# HM-Relais4-v01-002-Umrisse.net
KiCad netlist of a schematic drawn in EAGLE
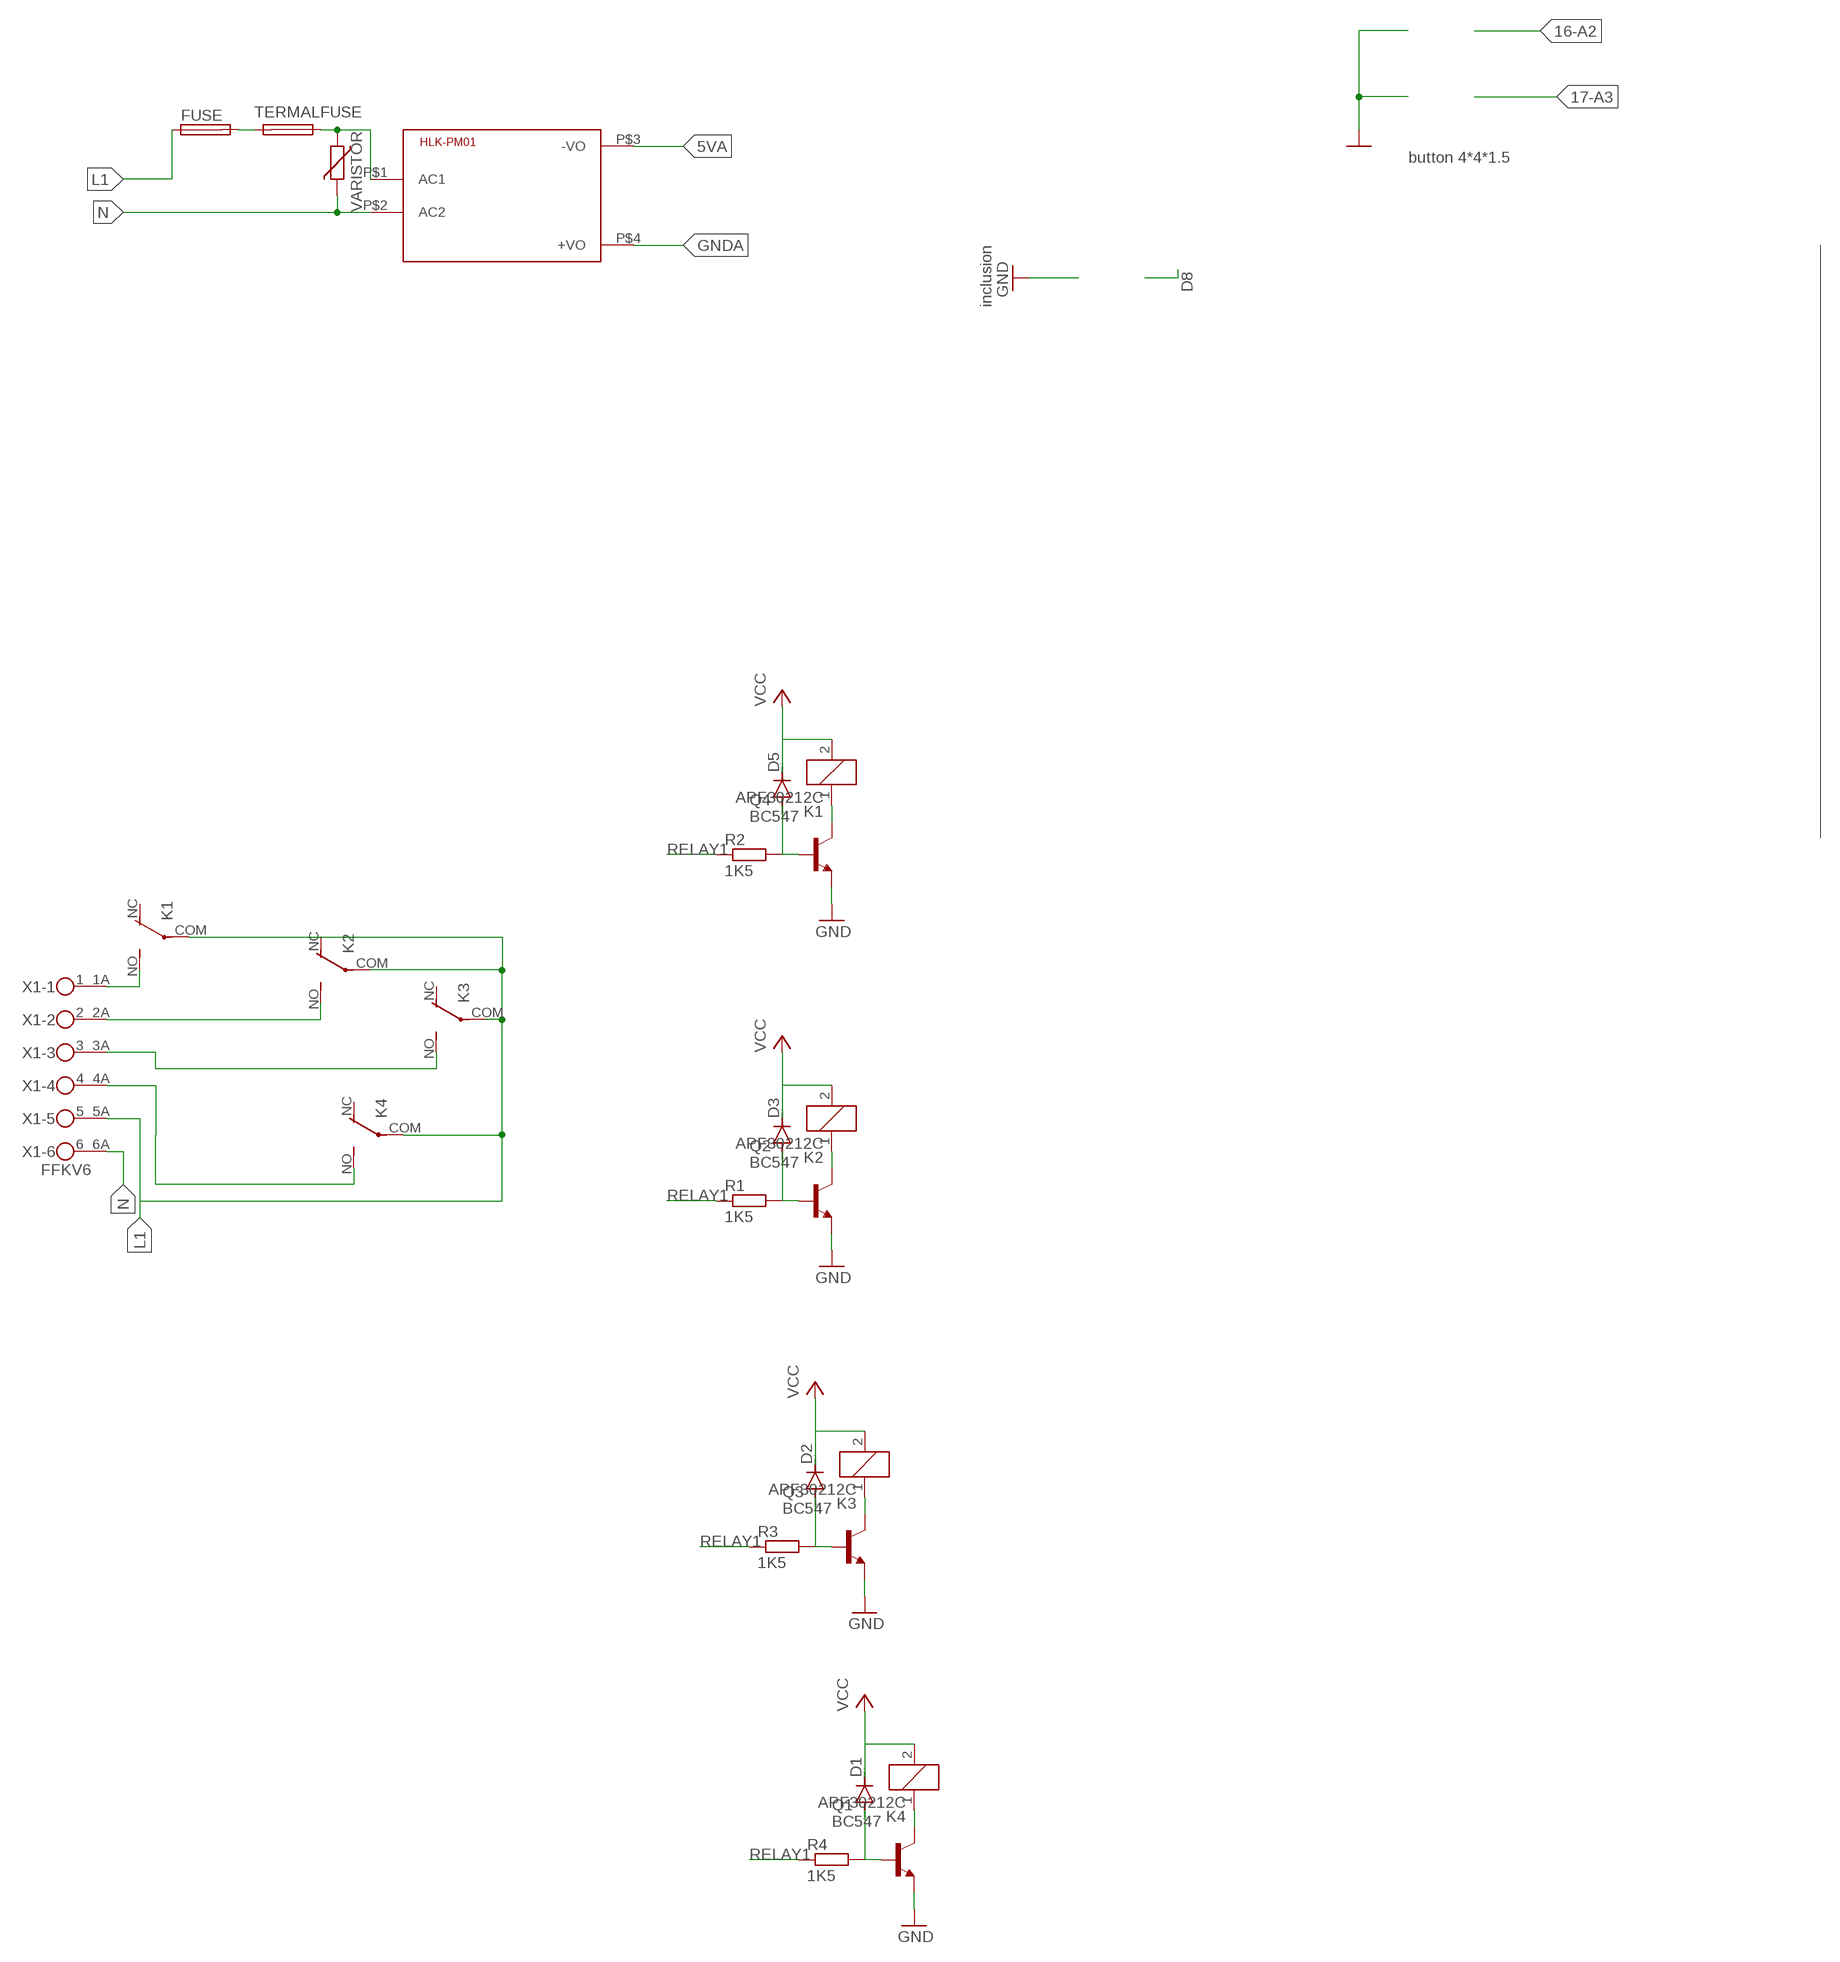
[diagram p0: schematic, sheet 1]

(export (version "E")
  (design (tool "Eeschema 10.0.6"))
  (components
    (comp (ref "D1")
      (value "DIODE-D-2.5")
      (footprint "eagle-import:D-2.5")
      (libsource (lib "eagle-import") (part "DIODE-D-2.5"))
    )
    (comp (ref "D2")
      (value "DIODE-D-2.5")
      (footprint "eagle-import:D-2.5")
      (libsource (lib "eagle-import") (part "DIODE-D-2.5"))
    )
    (comp (ref "D3")
      (value "DIODE-D-2.5")
      (footprint "eagle-import:D-2.5")
      (libsource (lib "eagle-import") (part "DIODE-D-2.5"))
    )
    (comp (ref "D5")
      (value "DIODE-D-2.5")
      (footprint "eagle-import:D-2.5")
      (libsource (lib "eagle-import") (part "DIODE-D-2.5"))
    )
    (comp (ref "FUSE")
      (value "FUSETE5")
      (footprint "eagle-import:TE5")
      (libsource (lib "eagle-import") (part "FUSETE5"))
    )
    (comp (ref "HLK-PM01")
      (value "HKLPM01")
      (footprint "eagle-import:HKLPM01")
      (libsource (lib "eagle-import") (part "HKLPM01"))
    )
    (comp (ref "K1")
      (value "APF30212C")
      (footprint "eagle-import:APF30212C")
      (libsource (lib "eagle-import") (part "APF30212C"))
    )
    (comp (ref "K2")
      (value "APF30212C")
      (footprint "eagle-import:APF30212C")
      (libsource (lib "eagle-import") (part "APF30212C"))
    )
    (comp (ref "K3")
      (value "APF30212C")
      (footprint "eagle-import:APF30212C")
      (libsource (lib "eagle-import") (part "APF30212C"))
    )
    (comp (ref "K4")
      (value "APF30212C")
      (footprint "eagle-import:APF30212C")
      (libsource (lib "eagle-import") (part "APF30212C"))
    )
    (comp (ref "Q1")
      (value "BC547")
      (footprint "eagle-import:TO92")
      (libsource (lib "eagle-import") (part "BC547"))
    )
    (comp (ref "Q2")
      (value "BC547")
      (footprint "eagle-import:TO92")
      (libsource (lib "eagle-import") (part "BC547"))
    )
    (comp (ref "Q3")
      (value "BC547")
      (footprint "eagle-import:TO92")
      (libsource (lib "eagle-import") (part "BC547"))
    )
    (comp (ref "Q4")
      (value "BC547")
      (footprint "eagle-import:TO92")
      (libsource (lib "eagle-import") (part "BC547"))
    )
    (comp (ref "R1")
      (value "1K5")
      (footprint "eagle-import:0207_2V")
      (libsource (lib "eagle-import") (part "R-EU_0207/2V"))
    )
    (comp (ref "R2")
      (value "1K5")
      (footprint "eagle-import:0207_2V")
      (libsource (lib "eagle-import") (part "R-EU_0207/2V"))
    )
    (comp (ref "R3")
      (value "1K5")
      (footprint "eagle-import:0207_2V")
      (libsource (lib "eagle-import") (part "R-EU_0207/2V"))
    )
    (comp (ref "R4")
      (value "1K5")
      (footprint "eagle-import:0207_2V")
      (libsource (lib "eagle-import") (part "R-EU_0207/2V"))
    )
    (comp (ref "TERMALFUSE")
      (value "FUSETE5")
      (footprint "eagle-import:TE5")
      (libsource (lib "eagle-import") (part "FUSETE5"))
    )
    (comp (ref "VARISTOR")
      (value "VARISTOR-7,5")
      (footprint "eagle-import:R-7,5")
      (libsource (lib "eagle-import") (part "VARISTOR-7,5"))
    )
    (comp (ref "X1")
      (value "FFKV6")
      (footprint "eagle-import:FFKV6")
      (libsource (lib "eagle-import") (part "FFKV6"))
    )
  )
  (nets
    (net (code "2") (name "/RELAY1") (class "Default")
      (node (ref "R1") (pin "1") (pinfunction "1_1") (pintype "passive"))
      (node (ref "R2") (pin "1") (pinfunction "1_1") (pintype "passive"))
      (node (ref "R3") (pin "1") (pinfunction "1_1") (pintype "passive"))
      (node (ref "R4") (pin "1") (pinfunction "1_1") (pintype "passive"))
    )
    (net (code "3") (name "5VA") (class "Default")
      (node (ref "HLK-PM01") (pin "P$3") (pinfunction "-VO_P$3") (pintype "bidirectional"))
    )
    (net (code "6") (name "GND") (class "Default")
      (node (ref "Q1") (pin "1") (pinfunction "E_1") (pintype "passive"))
      (node (ref "Q2") (pin "1") (pinfunction "E_1") (pintype "passive"))
      (node (ref "Q3") (pin "1") (pinfunction "E_1") (pintype "passive"))
      (node (ref "Q4") (pin "1") (pinfunction "E_1") (pintype "passive"))
    )
    (net (code "7") (name "GNDA") (class "Default")
      (node (ref "HLK-PM01") (pin "P$4") (pinfunction "+VO_P$4") (pintype "bidirectional"))
    )
    (net (code "8") (name "L1") (class "Default")
      (node (ref "FUSE") (pin "1") (pinfunction "1_1") (pintype "passive"))
      (node (ref "K1") (pin "COM") (pinfunction "P_COM") (pintype "passive"))
      (node (ref "K2") (pin "COM") (pinfunction "P_COM") (pintype "passive"))
      (node (ref "K3") (pin "COM") (pinfunction "P_COM") (pintype "passive"))
      (node (ref "K4") (pin "COM") (pinfunction "P_COM") (pintype "passive"))
      (node (ref "X1") (pin "5A") (pinfunction "2_5A") (pintype "passive"))
    )
    (net (code "9") (name "N") (class "Default")
      (node (ref "HLK-PM01") (pin "P$2") (pinfunction "AC2_P$2") (pintype "bidirectional"))
      (node (ref "VARISTOR") (pin "2") (pinfunction "2_2") (pintype "passive"))
      (node (ref "X1") (pin "6A") (pinfunction "2_6A") (pintype "passive"))
    )
    (net (code "10") (name "Net-(FUSE-Pad2)") (class "Default")
      (node (ref "FUSE") (pin "2") (pinfunction "2_2") (pintype "passive"))
      (node (ref "TERMALFUSE") (pin "2") (pinfunction "2_2") (pintype "passive"))
    )
    (net (code "11") (name "Net-(HLK-PM01-AC1)") (class "Default")
      (node (ref "HLK-PM01") (pin "P$1") (pinfunction "AC1_P$1") (pintype "bidirectional"))
      (node (ref "TERMALFUSE") (pin "1") (pinfunction "1_1") (pintype "passive"))
      (node (ref "VARISTOR") (pin "1") (pinfunction "1_1") (pintype "passive"))
    )
    (net (code "12") (name "Net-(K1B-S)") (class "Default")
      (node (ref "K1") (pin "NO") (pinfunction "S_NO") (pintype "passive"))
      (node (ref "X1") (pin "1A") (pinfunction "2_1A") (pintype "passive"))
    )
    (net (code "13") (name "Net-(K2B-S)") (class "Default")
      (node (ref "K2") (pin "NO") (pinfunction "S_NO") (pintype "passive"))
      (node (ref "X1") (pin "2A") (pinfunction "2_2A") (pintype "passive"))
    )
    (net (code "14") (name "Net-(K3B-S)") (class "Default")
      (node (ref "K3") (pin "NO") (pinfunction "S_NO") (pintype "passive"))
      (node (ref "X1") (pin "3A") (pinfunction "2_3A") (pintype "passive"))
    )
    (net (code "15") (name "Net-(K4B-S)") (class "Default")
      (node (ref "K4") (pin "NO") (pinfunction "S_NO") (pintype "passive"))
      (node (ref "X1") (pin "4A") (pinfunction "2_4A") (pintype "passive"))
    )
    (net (code "16") (name "Net-(Q1-B)") (class "Default")
      (node (ref "D1") (pin "A") (pinfunction "A_A") (pintype "passive"))
      (node (ref "Q1") (pin "2") (pinfunction "B_2") (pintype "passive"))
      (node (ref "R4") (pin "2") (pinfunction "2_2") (pintype "passive"))
    )
    (net (code "17") (name "Net-(Q1-C)") (class "Default")
      (node (ref "K4") (pin "1") (pinfunction "1_1") (pintype "passive"))
      (node (ref "Q1") (pin "3") (pinfunction "C_3") (pintype "passive"))
    )
    (net (code "18") (name "Net-(Q2-B)") (class "Default")
      (node (ref "D3") (pin "A") (pinfunction "A_A") (pintype "passive"))
      (node (ref "Q2") (pin "2") (pinfunction "B_2") (pintype "passive"))
      (node (ref "R1") (pin "2") (pinfunction "2_2") (pintype "passive"))
    )
    (net (code "19") (name "Net-(Q2-C)") (class "Default")
      (node (ref "K2") (pin "1") (pinfunction "1_1") (pintype "passive"))
      (node (ref "Q2") (pin "3") (pinfunction "C_3") (pintype "passive"))
    )
    (net (code "20") (name "Net-(Q3-B)") (class "Default")
      (node (ref "D2") (pin "A") (pinfunction "A_A") (pintype "passive"))
      (node (ref "Q3") (pin "2") (pinfunction "B_2") (pintype "passive"))
      (node (ref "R3") (pin "2") (pinfunction "2_2") (pintype "passive"))
    )
    (net (code "21") (name "Net-(Q3-C)") (class "Default")
      (node (ref "K3") (pin "1") (pinfunction "1_1") (pintype "passive"))
      (node (ref "Q3") (pin "3") (pinfunction "C_3") (pintype "passive"))
    )
    (net (code "22") (name "Net-(Q4-B)") (class "Default")
      (node (ref "D5") (pin "A") (pinfunction "A_A") (pintype "passive"))
      (node (ref "Q4") (pin "2") (pinfunction "B_2") (pintype "passive"))
      (node (ref "R2") (pin "2") (pinfunction "2_2") (pintype "passive"))
    )
    (net (code "23") (name "Net-(Q4-C)") (class "Default")
      (node (ref "K1") (pin "1") (pinfunction "1_1") (pintype "passive"))
      (node (ref "Q4") (pin "3") (pinfunction "C_3") (pintype "passive"))
    )
    (net (code "24") (name "VCC") (class "Default")
      (node (ref "D1") (pin "C") (pinfunction "C_C") (pintype "passive"))
      (node (ref "D2") (pin "C") (pinfunction "C_C") (pintype "passive"))
      (node (ref "D3") (pin "C") (pinfunction "C_C") (pintype "passive"))
      (node (ref "D5") (pin "C") (pinfunction "C_C") (pintype "passive"))
      (node (ref "K1") (pin "2") (pinfunction "2_2") (pintype "passive"))
      (node (ref "K2") (pin "2") (pinfunction "2_2") (pintype "passive"))
      (node (ref "K3") (pin "2") (pinfunction "2_2") (pintype "passive"))
      (node (ref "K4") (pin "2") (pinfunction "2_2") (pintype "passive"))
    )
    (net (code "25") (name "unconnected-(K1B-O-PadNC)") (class "Default")
      (node (ref "K1") (pin "NC") (pinfunction "O_NC") (pintype "passive"))
    )
    (net (code "26") (name "unconnected-(K2B-O-PadNC)") (class "Default")
      (node (ref "K2") (pin "NC") (pinfunction "O_NC") (pintype "passive"))
    )
    (net (code "27") (name "unconnected-(K3B-O-PadNC)") (class "Default")
      (node (ref "K3") (pin "NC") (pinfunction "O_NC") (pintype "passive"))
    )
    (net (code "28") (name "unconnected-(K4B-O-PadNC)") (class "Default")
      (node (ref "K4") (pin "NC") (pinfunction "O_NC") (pintype "passive"))
    )
    (net (code "29") (name "unconnected-(X1-Pad1)") (class "Default")
      (node (ref "X1") (pin "1") (pinfunction "1_1") (pintype "passive"))
    )
    (net (code "30") (name "unconnected-(X1B-1-Pad2)") (class "Default")
      (node (ref "X1") (pin "2") (pinfunction "1_2") (pintype "passive"))
    )
    (net (code "31") (name "unconnected-(X1C-1-Pad3)") (class "Default")
      (node (ref "X1") (pin "3") (pinfunction "1_3") (pintype "passive"))
    )
    (net (code "32") (name "unconnected-(X1D-1-Pad4)") (class "Default")
      (node (ref "X1") (pin "4") (pinfunction "1_4") (pintype "passive"))
    )
    (net (code "33") (name "unconnected-(X1E-1-Pad5)") (class "Default")
      (node (ref "X1") (pin "5") (pinfunction "1_5") (pintype "passive"))
    )
    (net (code "34") (name "unconnected-(X1F-1-Pad6)") (class "Default")
      (node (ref "X1") (pin "6") (pinfunction "1_6") (pintype "passive"))
    )
  )
)
